# schema.net
KiCad netlist of a schematic drawn in EAGLE
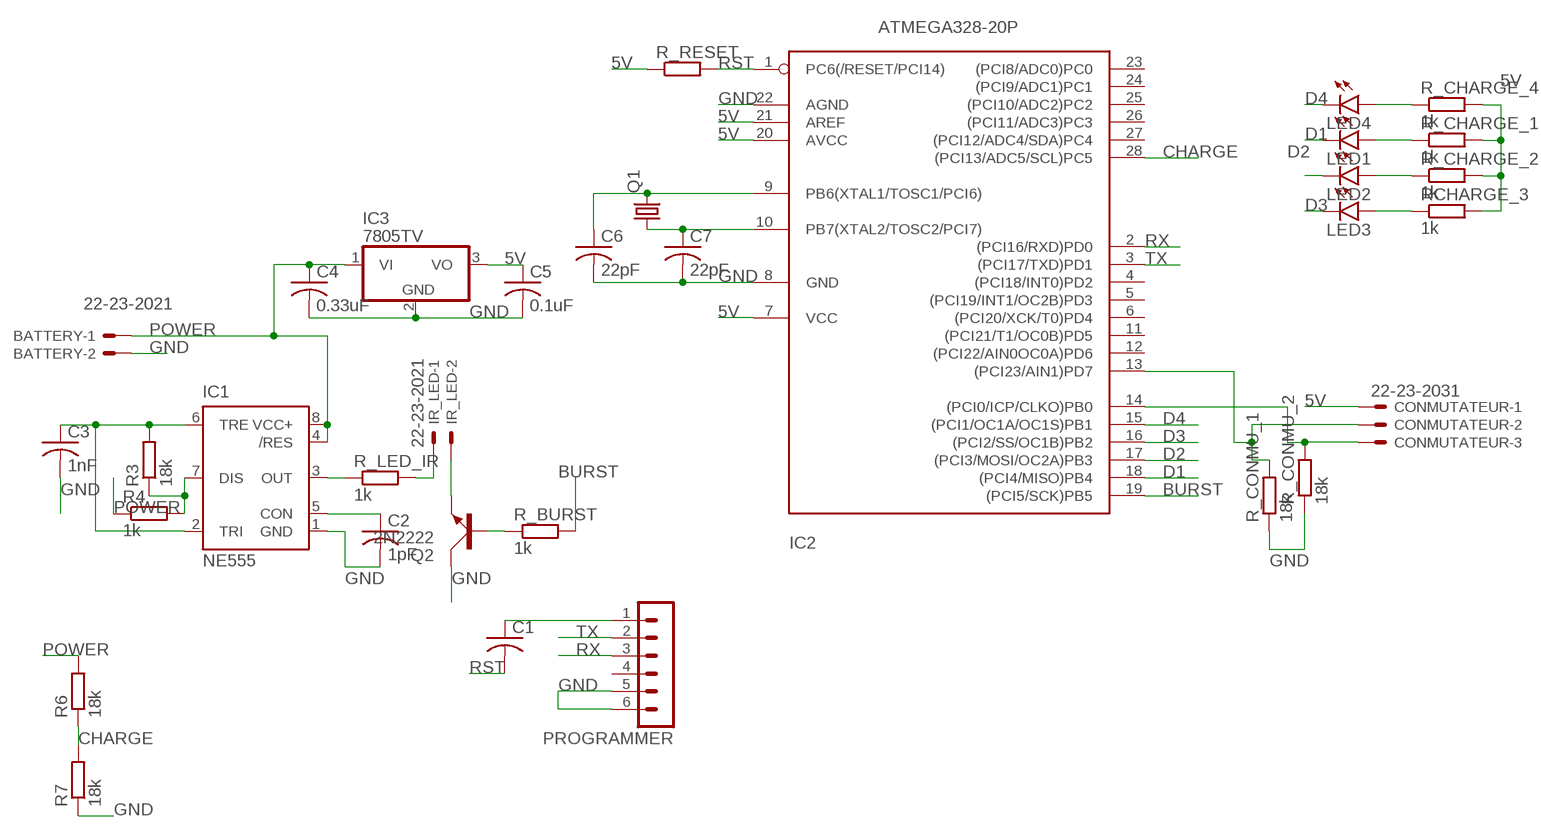
[diagram p0: schematic, sheet 1]

(export (version "E")
  (design (tool "Eeschema 10.0.6"))
  (components
    (comp (ref "BATTERY")
      (value "22-23-2021")
      (footprint "eagle-import:22-23-2021")
      (fields (field (name "MF") "MOLEX"))
      (libsource (lib "eagle-import") (part "22-23-2021"))
    )
    (comp (ref "C1")
      (value "C-US050-024X044")
      (footprint "eagle-import:C050-024X044")
      (libsource (lib "eagle-import") (part "C-US050-024X044"))
    )
    (comp (ref "C2")
      (value "1pF")
      (footprint "eagle-import:C050-024X044")
      (libsource (lib "eagle-import") (part "C-US050-024X044"))
    )
    (comp (ref "C3")
      (value "1nF")
      (footprint "eagle-import:C050-024X044")
      (libsource (lib "eagle-import") (part "C-US050-024X044"))
    )
    (comp (ref "C4")
      (value "0.33uF")
      (footprint "eagle-import:C050-024X044")
      (libsource (lib "eagle-import") (part "C-US050-024X044"))
    )
    (comp (ref "C5")
      (value "0.1uF")
      (footprint "eagle-import:C050-024X044")
      (libsource (lib "eagle-import") (part "C-US050-024X044"))
    )
    (comp (ref "C6")
      (value "22pF")
      (footprint "eagle-import:C050-024X044")
      (libsource (lib "eagle-import") (part "C-US050-024X044"))
    )
    (comp (ref "C7")
      (value "22pF")
      (footprint "eagle-import:C050-024X044")
      (libsource (lib "eagle-import") (part "C-US050-024X044"))
    )
    (comp (ref "CONMUTATEUR")
      (value "22-23-2031")
      (footprint "eagle-import:22-23-2031")
      (fields (field (name "MF") "MOLEX"))
      (libsource (lib "eagle-import") (part "22-23-2031"))
    )
    (comp (ref "IC1")
      (value "NE555")
      (footprint "eagle-import:DIL-08")
      (fields (field (name "MF") "Arrow Electronics") (field (name "MPN") "NE555N"))
      (libsource (lib "eagle-import") (part "NE555"))
    )
    (comp (ref "IC2")
      (value "ATMEGA328-20P")
      (footprint "eagle-import:DIL28-3")
      (libsource (lib "eagle-import") (part "ATMEGA328P-20"))
    )
    (comp (ref "IC3")
      (value "7805TV")
      (footprint "eagle-import:TO220V")
      (libsource (lib "eagle-import") (part "78TV05"))
    )
    (comp (ref "IR_LED")
      (value "22-23-2021")
      (footprint "eagle-import:22-23-2021")
      (fields (field (name "MF") "MOLEX"))
      (libsource (lib "eagle-import") (part "22-23-2021"))
    )
    (comp (ref "LED1")
      (value "LED5MM")
      (footprint "eagle-import:LED5MM")
      (libsource (lib "eagle-import") (part "LED5MM"))
    )
    (comp (ref "LED2")
      (value "LED5MM")
      (footprint "eagle-import:LED5MM")
      (libsource (lib "eagle-import") (part "LED5MM"))
    )
    (comp (ref "LED3")
      (value "LED5MM")
      (footprint "eagle-import:LED5MM")
      (libsource (lib "eagle-import") (part "LED5MM"))
    )
    (comp (ref "LED4")
      (value "LED5MM")
      (footprint "eagle-import:LED5MM")
      (libsource (lib "eagle-import") (part "LED5MM"))
    )
    (comp (ref "PROGRAMMER")
      (value "MA06-1")
      (footprint "eagle-import:MA06-1")
      (libsource (lib "eagle-import") (part "MA06-1"))
    )
    (comp (ref "Q1")
      (value "CRYSTALHC49S")
      (footprint "eagle-import:HC49_S")
      (libsource (lib "eagle-import") (part "CRYSTALHC49S"))
    )
    (comp (ref "Q2")
      (value "2N2222")
      (footprint "eagle-import:TO18A")
      (libsource (lib "eagle-import") (part "2N2222"))
    )
    (comp (ref "R3")
      (value "18k")
      (footprint "eagle-import:0207_7")
      (libsource (lib "eagle-import") (part "R-EU_0207/7"))
    )
    (comp (ref "R4")
      (value "1k")
      (footprint "eagle-import:0207_7")
      (libsource (lib "eagle-import") (part "R-EU_0207/7"))
    )
    (comp (ref "R6")
      (value "18k")
      (footprint "eagle-import:0207_7")
      (libsource (lib "eagle-import") (part "R-EU_0207/7"))
    )
    (comp (ref "R7")
      (value "18k")
      (footprint "eagle-import:0207_7")
      (libsource (lib "eagle-import") (part "R-EU_0207/7"))
    )
    (comp (ref "RCHARGE_3")
      (value "1k")
      (footprint "eagle-import:0207_7")
      (libsource (lib "eagle-import") (part "R-EU_0207/7"))
    )
    (comp (ref "R_BURST")
      (value "1k")
      (footprint "eagle-import:0207_7")
      (libsource (lib "eagle-import") (part "R-EU_0207/7"))
    )
    (comp (ref "R_CHARGE_1")
      (value "1k")
      (footprint "eagle-import:0207_7")
      (libsource (lib "eagle-import") (part "R-EU_0207/7"))
    )
    (comp (ref "R_CHARGE_2")
      (value "1k")
      (footprint "eagle-import:0207_7")
      (libsource (lib "eagle-import") (part "R-EU_0207/7"))
    )
    (comp (ref "R_CHARGE_4")
      (value "1k")
      (footprint "eagle-import:0207_7")
      (libsource (lib "eagle-import") (part "R-EU_0207/7"))
    )
    (comp (ref "R_CONMU_1")
      (value "18k")
      (footprint "eagle-import:0207_7")
      (libsource (lib "eagle-import") (part "R-EU_0207/7"))
    )
    (comp (ref "R_CONMU_2")
      (value "18k")
      (footprint "eagle-import:0207_7")
      (libsource (lib "eagle-import") (part "R-EU_0207/7"))
    )
    (comp (ref "R_LED_IR")
      (value "1k")
      (footprint "eagle-import:0207_7")
      (libsource (lib "eagle-import") (part "R-EU_0207/7"))
    )
    (comp (ref "R_RESET")
      (value "R-EU_0207/7")
      (footprint "eagle-import:0207_7")
      (libsource (lib "eagle-import") (part "R-EU_0207/7"))
    )
  )
  (nets
    (net (code "1") (name "/5V") (class "Default")
      (node (ref "C5") (pin "1") (pinfunction "1_1") (pintype "passive"))
      (node (ref "CONMUTATEUR") (pin "1") (pinfunction "S_1") (pintype "passive"))
      (node (ref "IC2") (pin "20") (pinfunction "AVCC_20") (pintype "bidirectional"))
      (node (ref "IC2") (pin "21") (pinfunction "AREF_21") (pintype "bidirectional"))
      (node (ref "IC2") (pin "7") (pinfunction "VCC_7") (pintype "bidirectional"))
      (node (ref "IC3") (pin "3") (pinfunction "VO_3") (pintype "passive"))
      (node (ref "RCHARGE_3") (pin "2") (pinfunction "2_2") (pintype "passive"))
      (node (ref "R_CHARGE_1") (pin "2") (pinfunction "2_2") (pintype "passive"))
      (node (ref "R_CHARGE_2") (pin "2") (pinfunction "2_2") (pintype "passive"))
      (node (ref "R_CHARGE_4") (pin "2") (pinfunction "2_2") (pintype "passive"))
      (node (ref "R_RESET") (pin "1") (pinfunction "1_1") (pintype "passive"))
    )
    (net (code "2") (name "/BURST") (class "Default")
      (node (ref "IC2") (pin "19") (pinfunction "(PCI5/SCK)PB5_19") (pintype "bidirectional"))
      (node (ref "R_BURST") (pin "2") (pinfunction "2_2") (pintype "passive"))
    )
    (net (code "3") (name "/CHARGE") (class "Default")
      (node (ref "IC2") (pin "28") (pinfunction "(PCI13/ADC5/SCL)PC5_28") (pintype "bidirectional"))
      (node (ref "R6") (pin "1") (pinfunction "1_1") (pintype "passive"))
      (node (ref "R7") (pin "2") (pinfunction "2_2") (pintype "passive"))
    )
    (net (code "4") (name "/D1") (class "Default")
      (node (ref "IC2") (pin "18") (pinfunction "(PCI4/MISO)PB4_18") (pintype "bidirectional"))
      (node (ref "LED1") (pin "K") (pinfunction "C_K") (pintype "passive"))
    )
    (net (code "5") (name "/D2") (class "Default")
      (node (ref "IC2") (pin "17") (pinfunction "(PCI3/MOSI/OC2A)PB3_17") (pintype "bidirectional"))
      (node (ref "LED2") (pin "K") (pinfunction "C_K") (pintype "passive"))
    )
    (net (code "6") (name "/D3") (class "Default")
      (node (ref "IC2") (pin "16") (pinfunction "(PCI2/SS/OC1B)PB2_16") (pintype "bidirectional"))
      (node (ref "LED3") (pin "K") (pinfunction "C_K") (pintype "passive"))
    )
    (net (code "7") (name "/D4") (class "Default")
      (node (ref "IC2") (pin "15") (pinfunction "(PCI1/OC1A/OC1S)PB1_15") (pintype "bidirectional"))
      (node (ref "LED4") (pin "K") (pinfunction "C_K") (pintype "passive"))
    )
    (net (code "8") (name "/GND") (class "Default")
      (node (ref "BATTERY") (pin "2") (pinfunction "S_2") (pintype "passive"))
      (node (ref "C2") (pin "2") (pinfunction "2_2") (pintype "passive"))
      (node (ref "C3") (pin "2") (pinfunction "2_2") (pintype "passive"))
      (node (ref "C4") (pin "2") (pinfunction "2_2") (pintype "passive"))
      (node (ref "C5") (pin "2") (pinfunction "2_2") (pintype "passive"))
      (node (ref "C6") (pin "2") (pinfunction "2_2") (pintype "passive"))
      (node (ref "C7") (pin "2") (pinfunction "2_2") (pintype "passive"))
      (node (ref "IC1") (pin "1") (pinfunction "GND_1") (pintype "power_in"))
      (node (ref "IC2") (pin "22") (pinfunction "AGND_22") (pintype "bidirectional"))
      (node (ref "IC2") (pin "8") (pinfunction "GND_8") (pintype "bidirectional"))
      (node (ref "IC3") (pin "2") (pinfunction "GND_2") (pintype "passive"))
      (node (ref "PROGRAMMER") (pin "5") (pinfunction "5_5") (pintype "passive"))
      (node (ref "PROGRAMMER") (pin "6") (pinfunction "6_6") (pintype "passive"))
      (node (ref "Q2") (pin "C") (pinfunction "C_C") (pintype "passive"))
      (node (ref "R7") (pin "1") (pinfunction "1_1") (pintype "passive"))
      (node (ref "R_CONMU_1") (pin "1") (pinfunction "1_1") (pintype "passive"))
      (node (ref "R_CONMU_2") (pin "1") (pinfunction "1_1") (pintype "passive"))
    )
    (net (code "9") (name "/POWER") (class "Default")
      (node (ref "BATTERY") (pin "1") (pinfunction "S_1") (pintype "passive"))
      (node (ref "C4") (pin "1") (pinfunction "1_1") (pintype "passive"))
      (node (ref "IC1") (pin "4") (pinfunction "/RES_4") (pintype "input"))
      (node (ref "IC1") (pin "8") (pinfunction "VCC+_8") (pintype "power_in"))
      (node (ref "IC3") (pin "1") (pinfunction "VI_1") (pintype "input"))
      (node (ref "R4") (pin "1") (pinfunction "1_1") (pintype "passive"))
      (node (ref "R6") (pin "2") (pinfunction "2_2") (pintype "passive"))
    )
    (net (code "10") (name "/RST") (class "Default")
      (node (ref "C1") (pin "2") (pinfunction "2_2") (pintype "passive"))
      (node (ref "IC2") (pin "1") (pinfunction "PC6(/RESET/PCI14)_1") (pintype "bidirectional"))
      (node (ref "R_RESET") (pin "2") (pinfunction "2_2") (pintype "passive"))
    )
    (net (code "11") (name "/RX") (class "Default")
      (node (ref "IC2") (pin "2") (pinfunction "(PCI16/RXD)PD0_2") (pintype "bidirectional"))
      (node (ref "PROGRAMMER") (pin "3") (pinfunction "3_3") (pintype "passive"))
    )
    (net (code "12") (name "/TX") (class "Default")
      (node (ref "IC2") (pin "3") (pinfunction "(PCI17/TXD)PD1_3") (pintype "bidirectional"))
      (node (ref "PROGRAMMER") (pin "2") (pinfunction "2_2") (pintype "passive"))
    )
    (net (code "13") (name "Net-(C1-Pad1)") (class "Default")
      (node (ref "C1") (pin "1") (pinfunction "1_1") (pintype "passive"))
      (node (ref "PROGRAMMER") (pin "1") (pinfunction "1_1") (pintype "passive"))
    )
    (net (code "14") (name "Net-(CONMUTATEURB-S)") (class "Default")
      (node (ref "CONMUTATEUR") (pin "2") (pinfunction "S_2") (pintype "passive"))
      (node (ref "IC2") (pin "13") (pinfunction "(PCI23/AIN1)PD7_13") (pintype "bidirectional"))
      (node (ref "R_CONMU_1") (pin "2") (pinfunction "2_2") (pintype "passive"))
    )
    (net (code "15") (name "Net-(CONMUTATEURC-S)") (class "Default")
      (node (ref "CONMUTATEUR") (pin "3") (pinfunction "S_3") (pintype "passive"))
      (node (ref "IC2") (pin "14") (pinfunction "(PCI0/ICP/CLKO)PB0_14") (pintype "bidirectional"))
      (node (ref "R_CONMU_2") (pin "2") (pinfunction "2_2") (pintype "passive"))
    )
    (net (code "16") (name "Net-(IC1-CON)") (class "Default")
      (node (ref "C2") (pin "1") (pinfunction "1_1") (pintype "passive"))
      (node (ref "IC1") (pin "5") (pinfunction "CON_5") (pintype "input"))
    )
    (net (code "17") (name "Net-(IC1-DIS)") (class "Default")
      (node (ref "IC1") (pin "7") (pinfunction "DIS_7") (pintype "input"))
      (node (ref "R3") (pin "1") (pinfunction "1_1") (pintype "passive"))
      (node (ref "R4") (pin "2") (pinfunction "2_2") (pintype "passive"))
    )
    (net (code "18") (name "Net-(IC1-OUT)") (class "Default")
      (node (ref "IC1") (pin "3") (pinfunction "OUT_3") (pintype "output"))
      (node (ref "R_LED_IR") (pin "1") (pinfunction "1_1") (pintype "passive"))
    )
    (net (code "19") (name "Net-(IC1-TRE)") (class "Default")
      (node (ref "C3") (pin "1") (pinfunction "1_1") (pintype "passive"))
      (node (ref "IC1") (pin "2") (pinfunction "TRI_2") (pintype "input"))
      (node (ref "IC1") (pin "6") (pinfunction "TRE_6") (pintype "input"))
      (node (ref "R3") (pin "2") (pinfunction "2_2") (pintype "passive"))
    )
    (net (code "20") (name "Net-(IC2-PB6(XTAL1{slash}TOSC1{slash}PCI6))") (class "Default")
      (node (ref "C6") (pin "1") (pinfunction "1_1") (pintype "passive"))
      (node (ref "IC2") (pin "9") (pinfunction "PB6(XTAL1/TOSC1/PCI6)_9") (pintype "bidirectional"))
      (node (ref "Q1") (pin "2") (pinfunction "2_2") (pintype "passive"))
    )
    (net (code "21") (name "Net-(IC2-PB7(XTAL2{slash}TOSC2{slash}PCI7))") (class "Default")
      (node (ref "C7") (pin "1") (pinfunction "1_1") (pintype "passive"))
      (node (ref "IC2") (pin "10") (pinfunction "PB7(XTAL2/TOSC2/PCI7)_10") (pintype "bidirectional"))
      (node (ref "Q1") (pin "1") (pinfunction "1_1") (pintype "passive"))
    )
    (net (code "22") (name "Net-(IR_LEDA-S)") (class "Default")
      (node (ref "IR_LED") (pin "1") (pinfunction "S_1") (pintype "passive"))
      (node (ref "R_LED_IR") (pin "2") (pinfunction "2_2") (pintype "passive"))
    )
    (net (code "23") (name "Net-(IR_LEDB-S)") (class "Default")
      (node (ref "IR_LED") (pin "2") (pinfunction "S_2") (pintype "passive"))
      (node (ref "Q2") (pin "E") (pinfunction "E_E") (pintype "passive"))
    )
    (net (code "24") (name "Net-(LED1-PadA)") (class "Default")
      (node (ref "LED1") (pin "A") (pinfunction "A_A") (pintype "passive"))
      (node (ref "R_CHARGE_1") (pin "1") (pinfunction "1_1") (pintype "passive"))
    )
    (net (code "25") (name "Net-(LED2-PadA)") (class "Default")
      (node (ref "LED2") (pin "A") (pinfunction "A_A") (pintype "passive"))
      (node (ref "R_CHARGE_2") (pin "1") (pinfunction "1_1") (pintype "passive"))
    )
    (net (code "26") (name "Net-(LED3-PadA)") (class "Default")
      (node (ref "LED3") (pin "A") (pinfunction "A_A") (pintype "passive"))
      (node (ref "RCHARGE_3") (pin "1") (pinfunction "1_1") (pintype "passive"))
    )
    (net (code "27") (name "Net-(LED4-PadA)") (class "Default")
      (node (ref "LED4") (pin "A") (pinfunction "A_A") (pintype "passive"))
      (node (ref "R_CHARGE_4") (pin "1") (pinfunction "1_1") (pintype "passive"))
    )
    (net (code "28") (name "Net-(Q2-PadB)") (class "Default")
      (node (ref "Q2") (pin "B") (pinfunction "B_B") (pintype "passive"))
      (node (ref "R_BURST") (pin "1") (pinfunction "1_1") (pintype "passive"))
    )
    (net (code "29") (name "unconnected-(IC2-(PCI8{slash}ADC0)PC0-Pad23)") (class "Default")
      (node (ref "IC2") (pin "23") (pinfunction "(PCI8/ADC0)PC0_23") (pintype "bidirectional"))
    )
    (net (code "30") (name "unconnected-(IC2-(PCI9{slash}ADC1)PC1-Pad24)") (class "Default")
      (node (ref "IC2") (pin "24") (pinfunction "(PCI9/ADC1)PC1_24") (pintype "bidirectional"))
    )
    (net (code "31") (name "unconnected-(IC2-(PCI10{slash}ADC2)PC2-Pad25)") (class "Default")
      (node (ref "IC2") (pin "25") (pinfunction "(PCI10/ADC2)PC2_25") (pintype "bidirectional"))
    )
    (net (code "32") (name "unconnected-(IC2-(PCI11{slash}ADC3)PC3-Pad26)") (class "Default")
      (node (ref "IC2") (pin "26") (pinfunction "(PCI11/ADC3)PC3_26") (pintype "bidirectional"))
    )
    (net (code "33") (name "unconnected-(IC2-(PCI12{slash}ADC4{slash}SDA)PC4-Pad27)") (class "Default")
      (node (ref "IC2") (pin "27") (pinfunction "(PCI12/ADC4/SDA)PC4_27") (pintype "bidirectional"))
    )
    (net (code "34") (name "unconnected-(IC2-(PCI18{slash}INT0)PD2-Pad4)") (class "Default")
      (node (ref "IC2") (pin "4") (pinfunction "(PCI18/INT0)PD2_4") (pintype "bidirectional"))
    )
    (net (code "35") (name "unconnected-(IC2-(PCI19{slash}INT1{slash}OC2B)PD3-Pad5)") (class "Default")
      (node (ref "IC2") (pin "5") (pinfunction "(PCI19/INT1/OC2B)PD3_5") (pintype "bidirectional"))
    )
    (net (code "36") (name "unconnected-(IC2-(PCI20{slash}XCK{slash}T0)PD4-Pad6)") (class "Default")
      (node (ref "IC2") (pin "6") (pinfunction "(PCI20/XCK/T0)PD4_6") (pintype "bidirectional"))
    )
    (net (code "37") (name "unconnected-(IC2-(PCI21{slash}T1{slash}OC0B)PD5-Pad11)") (class "Default")
      (node (ref "IC2") (pin "11") (pinfunction "(PCI21/T1/OC0B)PD5_11") (pintype "bidirectional"))
    )
    (net (code "38") (name "unconnected-(IC2-(PCI22{slash}AIN0OC0A)PD6-Pad12)") (class "Default")
      (node (ref "IC2") (pin "12") (pinfunction "(PCI22/AIN0OC0A)PD6_12") (pintype "bidirectional"))
    )
    (net (code "39") (name "unconnected-(PROGRAMMER-Pad4)") (class "Default")
      (node (ref "PROGRAMMER") (pin "4") (pinfunction "4_4") (pintype "passive"))
    )
  )
)
